# 07_Motion.net
KiCad netlist of a schematic drawn in Altium Designer
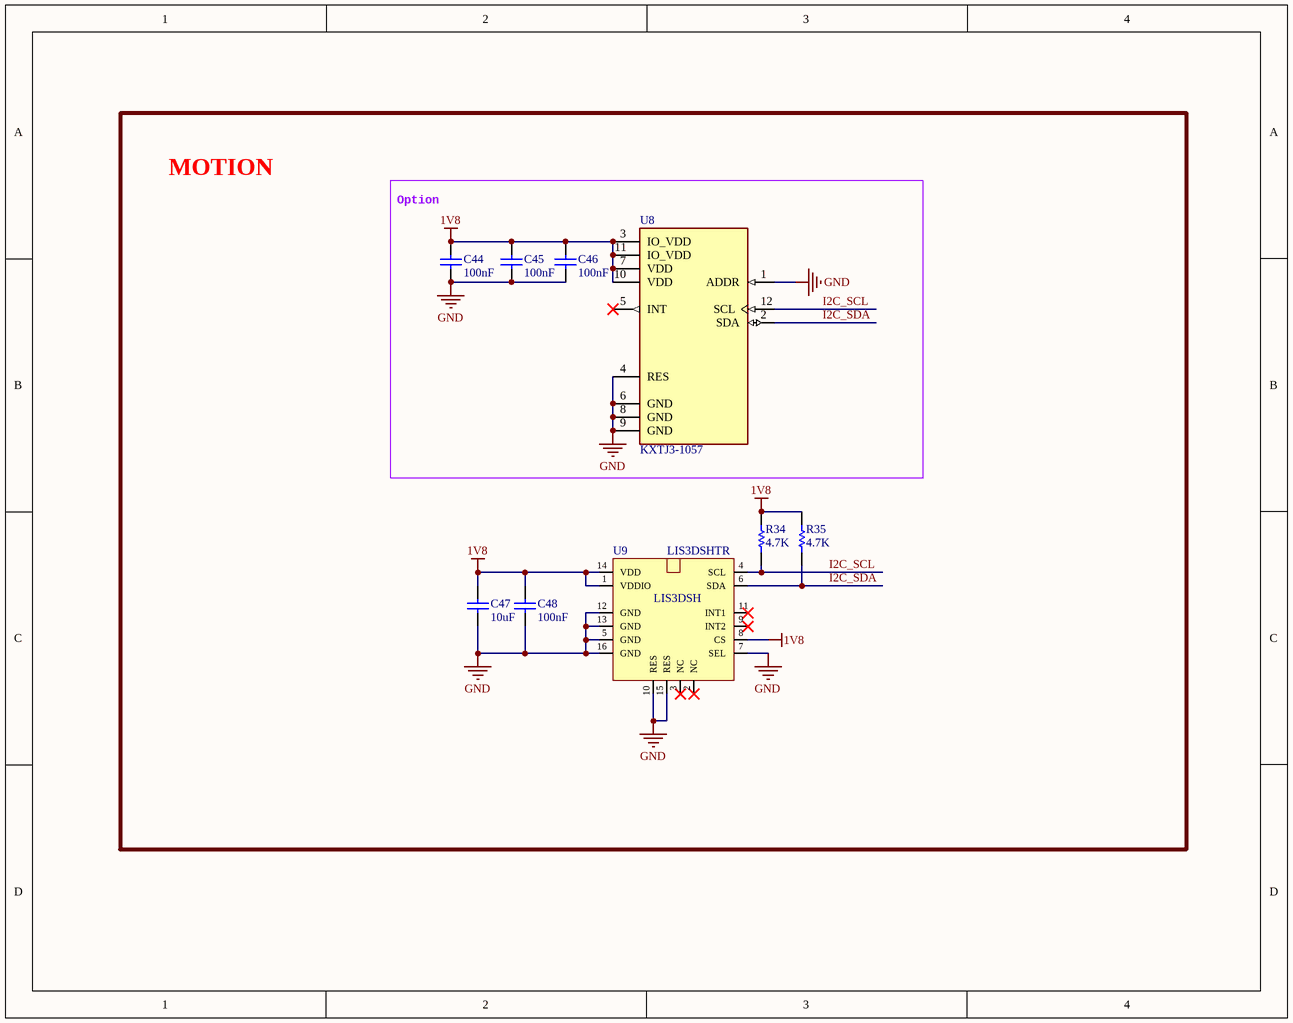
[diagram p0: 07 Motion.SchDoc]

(export (version "E")
  (design (tool "Eeschema 10.0.6"))
  (components
    (comp (ref "C44")
      (value "100nF")
      (footprint "0603 - C")
      (description "CAP CER 100nF 50V C0G/NP0 0603")
      (fields (field (name "MPN") "CL10C104JB8NNNC") (field (name "MFR") "SAMSUNG"))
      (libsource (lib "Library_Chip") (part "Cap 0603 100nF"))
    )
    (comp (ref "C45")
      (value "100nF")
      (footprint "0603 - C")
      (description "CAP CER 100nF 50V C0G/NP0 0603")
      (fields (field (name "MPN") "CL10C104JB8NNNC") (field (name "MFR") "SAMSUNG"))
      (libsource (lib "Library_Chip") (part "Cap 0603 100nF"))
    )
    (comp (ref "C46")
      (value "100nF")
      (footprint "0603 - C")
      (description "CAP CER 100nF 50V C0G/NP0 0603")
      (fields (field (name "MPN") "CL10C104JB8NNNC") (field (name "MFR") "SAMSUNG"))
      (libsource (lib "Library_Chip") (part "Cap 0603 100nF"))
    )
    (comp (ref "C47")
      (value "10uF")
      (footprint "0603 - C")
      (description "CAP CER 10UF 6.3V X5R 0603")
      (fields (field (name "MPN") "CC0603KRX5R5BB106") (field (name "MFR") "Yageo"))
      (libsource (lib "Library_Chip") (part "Cap 0603 10uF"))
    )
    (comp (ref "C48")
      (value "100nF")
      (footprint "0603 - C")
      (description "CAP CER 100nF 50V C0G/NP0 0603")
      (fields (field (name "MPN") "CL10C104JB8NNNC") (field (name "MFR") "SAMSUNG"))
      (libsource (lib "Library_Chip") (part "Cap 0603 100nF"))
    )
    (comp (ref "R34")
      (value "4.7K")
      (footprint "0603 - R")
      (description "RES SMD 4.7K OHM 1% 1/10W 0603")
      (fields (field (name "MFR") "Yageo") (field (name "MPN") "RC0603FR-074K7L"))
      (libsource (lib "Library_Chip") (part "Res 0603 4.7K"))
    )
    (comp (ref "R35")
      (value "4.7K")
      (footprint "0603 - R")
      (description "RES SMD 4.7K OHM 1% 1/10W 0603")
      (fields (field (name "MFR") "Yageo") (field (name "MPN") "RC0603FR-074K7L"))
      (libsource (lib "Library_Chip") (part "Res 0603 4.7K"))
    )
    (comp (ref "U8")
      (value "KXTJ3-1057")
      (footprint "KIONIX_KXTJ3-1057")
      (description "ACCELEROMETER 2-16G I2C 12LGA")
      (fields (field (name "MFR") "Kionix Inc."))
      (libsource (lib "KXTJ3-1057") (part "KXTJ3-1057"))
    )
    (comp (ref "U9")
      (value "LIS3DSHTR")
      (footprint "QFN16P 3x3 - 1")
      (description "ACCEL 2-16G I2C/SPI 16LGA")
      (fields (field (name "MFR") "ST"))
      (libsource (lib "Library_IC") (part "LIS3DSHTR"))
    )
  )
  (nets
    (net (code "1") (name "/I2C_SCL") (class "Default")
      (node (ref "R34") (pin "1") (pinfunction "1_1") (pintype "passive"))
      (node (ref "U8") (pin "12") (pinfunction "SCL_12") (pintype "input"))
      (node (ref "U9") (pin "4") (pinfunction "SCL_4") (pintype "passive"))
    )
    (net (code "2") (name "/I2C_SDA") (class "Default")
      (node (ref "R35") (pin "1") (pinfunction "1_1") (pintype "passive"))
      (node (ref "U8") (pin "2") (pinfunction "SDA_2") (pintype "bidirectional"))
      (node (ref "U9") (pin "6") (pinfunction "SDA_6") (pintype "passive"))
    )
    (net (code "3") (name "1V8") (class "Default")
      (node (ref "C44") (pin "2") (pinfunction "2_2") (pintype "passive"))
      (node (ref "C45") (pin "2") (pinfunction "2_2") (pintype "passive"))
      (node (ref "C46") (pin "2") (pinfunction "2_2") (pintype "passive"))
      (node (ref "C47") (pin "2") (pinfunction "2_2") (pintype "passive"))
      (node (ref "C48") (pin "2") (pinfunction "2_2") (pintype "passive"))
      (node (ref "R34") (pin "2") (pinfunction "2_2") (pintype "passive"))
      (node (ref "R35") (pin "2") (pinfunction "2_2") (pintype "passive"))
      (node (ref "U8") (pin "10") (pinfunction "VDD_10") (pintype "power_in"))
      (node (ref "U8") (pin "11") (pinfunction "IO_VDD_11") (pintype "power_in"))
      (node (ref "U8") (pin "3") (pinfunction "IO_VDD_3") (pintype "power_in"))
      (node (ref "U8") (pin "7") (pinfunction "VDD_7") (pintype "power_in"))
      (node (ref "U9") (pin "1") (pinfunction "VDDIO_1") (pintype "passive"))
      (node (ref "U9") (pin "14") (pinfunction "VDD_14") (pintype "passive"))
      (node (ref "U9") (pin "8") (pinfunction "CS_8") (pintype "passive"))
    )
    (net (code "4") (name "GND") (class "Default")
      (node (ref "C44") (pin "1") (pinfunction "1_1") (pintype "passive"))
      (node (ref "C45") (pin "1") (pinfunction "1_1") (pintype "passive"))
      (node (ref "C46") (pin "1") (pinfunction "1_1") (pintype "passive"))
      (node (ref "C47") (pin "1") (pinfunction "1_1") (pintype "passive"))
      (node (ref "C48") (pin "1") (pinfunction "1_1") (pintype "passive"))
      (node (ref "U8") (pin "1") (pinfunction "ADDR_1") (pintype "input"))
      (node (ref "U8") (pin "4") (pinfunction "RES_4") (pintype "passive"))
      (node (ref "U8") (pin "6") (pinfunction "GND_6") (pintype "power_in"))
      (node (ref "U8") (pin "8") (pinfunction "GND_8") (pintype "power_in"))
      (node (ref "U8") (pin "9") (pinfunction "GND_9") (pintype "power_in"))
      (node (ref "U9") (pin "10") (pinfunction "RES_10") (pintype "passive"))
      (node (ref "U9") (pin "12") (pinfunction "GND_12") (pintype "passive"))
      (node (ref "U9") (pin "13") (pinfunction "GND_13") (pintype "passive"))
      (node (ref "U9") (pin "15") (pinfunction "RES_15") (pintype "passive"))
      (node (ref "U9") (pin "16") (pinfunction "GND_16") (pintype "passive"))
      (node (ref "U9") (pin "5") (pinfunction "GND_5") (pintype "passive"))
      (node (ref "U9") (pin "7") (pinfunction "SEL_7") (pintype "passive"))
    )
    (net (code "5") (name "unconnected-(U8-INT-Pad5)") (class "Default")
      (node (ref "U8") (pin "5") (pinfunction "INT_5") (pintype "output+no_connect"))
    )
    (net (code "6") (name "unconnected-(U9-INT1-Pad11)") (class "Default")
      (node (ref "U9") (pin "11") (pinfunction "INT1_11") (pintype "passive+no_connect"))
    )
    (net (code "7") (name "unconnected-(U9-INT2-Pad9)") (class "Default")
      (node (ref "U9") (pin "9") (pinfunction "INT2_9") (pintype "passive+no_connect"))
    )
    (net (code "8") (name "unconnected-(U9-NC-Pad2)") (class "Default")
      (node (ref "U9") (pin "2") (pinfunction "NC_2") (pintype "passive+no_connect"))
    )
    (net (code "9") (name "unconnected-(U9-NC-Pad3)") (class "Default")
      (node (ref "U9") (pin "3") (pinfunction "NC_3") (pintype "passive+no_connect"))
    )
  )
)
